# LMH6881-Breakout_Single_Layer.net
KiCad netlist of a schematic drawn in EAGLE
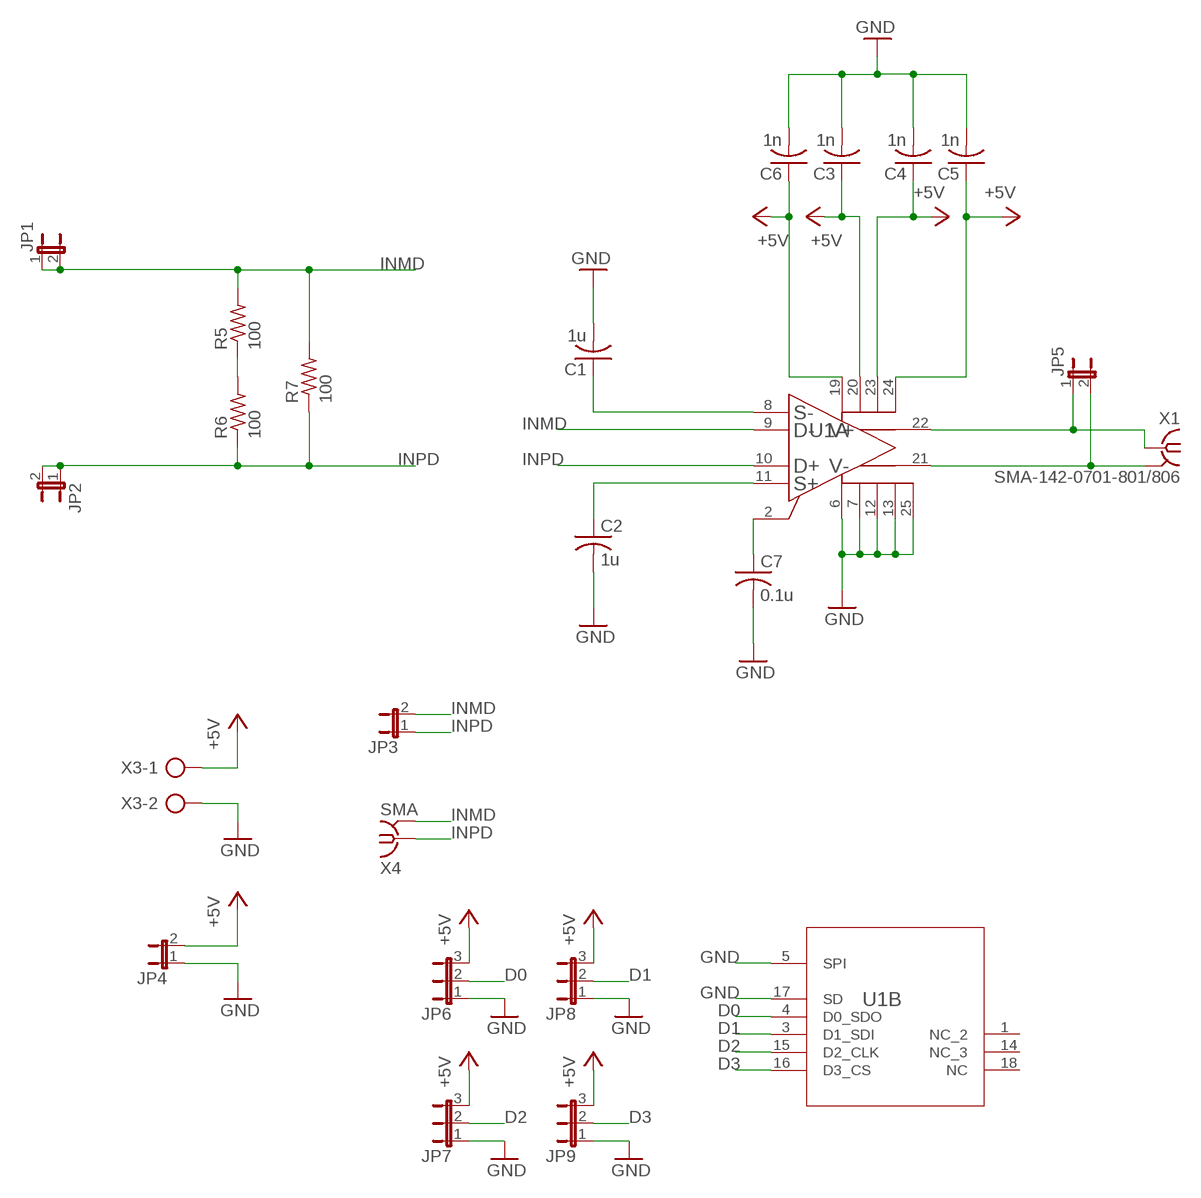
[diagram p0: schematic, sheet 1]

(export (version "E")
  (design (tool "Eeschema 10.0.6"))
  (components
    (comp (ref "C1")
      (value "1u")
      (footprint "eagle-import:C0805")
      (libsource (lib "eagle-import") (part "C-USC0805"))
    )
    (comp (ref "C2")
      (value "1u")
      (footprint "eagle-import:C0805")
      (libsource (lib "eagle-import") (part "C-USC0805"))
    )
    (comp (ref "C3")
      (value "1n")
      (footprint "eagle-import:C0805")
      (libsource (lib "eagle-import") (part "C-USC0805"))
    )
    (comp (ref "C4")
      (value "1n")
      (footprint "eagle-import:C0805")
      (libsource (lib "eagle-import") (part "C-USC0805"))
    )
    (comp (ref "C5")
      (value "1n")
      (footprint "eagle-import:C0805")
      (libsource (lib "eagle-import") (part "C-USC0805"))
    )
    (comp (ref "C6")
      (value "1n")
      (footprint "eagle-import:C0805")
      (libsource (lib "eagle-import") (part "C-USC0805"))
    )
    (comp (ref "C7")
      (value "0.1u")
      (footprint "eagle-import:C0805")
      (libsource (lib "eagle-import") (part "C-USC0805"))
    )
    (comp (ref "JP1")
      (value "JP1E")
      (footprint "eagle-import:JP1")
      (libsource (lib "eagle-import") (part "JP1E"))
    )
    (comp (ref "JP2")
      (value "JP1E")
      (footprint "eagle-import:JP1")
      (libsource (lib "eagle-import") (part "JP1E"))
    )
    (comp (ref "JP3")
      (value "JP1E")
      (footprint "eagle-import:JP1")
      (libsource (lib "eagle-import") (part "JP1E"))
    )
    (comp (ref "JP4")
      (value "JP1E")
      (footprint "eagle-import:JP1")
      (libsource (lib "eagle-import") (part "JP1E"))
    )
    (comp (ref "JP5")
      (value "JP1E")
      (footprint "eagle-import:JP1")
      (libsource (lib "eagle-import") (part "JP1E"))
    )
    (comp (ref "JP6")
      (value "JP2E")
      (footprint "eagle-import:JP2")
      (libsource (lib "eagle-import") (part "JP2E"))
    )
    (comp (ref "JP7")
      (value "JP2E")
      (footprint "eagle-import:JP2")
      (libsource (lib "eagle-import") (part "JP2E"))
    )
    (comp (ref "JP8")
      (value "JP2E")
      (footprint "eagle-import:JP2")
      (libsource (lib "eagle-import") (part "JP2E"))
    )
    (comp (ref "JP9")
      (value "JP2E")
      (footprint "eagle-import:JP2")
      (libsource (lib "eagle-import") (part "JP2E"))
    )
    (comp (ref "R5")
      (value "100")
      (footprint "eagle-import:R0805")
      (libsource (lib "eagle-import") (part "R-US_R0805"))
    )
    (comp (ref "R6")
      (value "100")
      (footprint "eagle-import:R0805")
      (libsource (lib "eagle-import") (part "R-US_R0805"))
    )
    (comp (ref "R7")
      (value "100")
      (footprint "eagle-import:R0805")
      (libsource (lib "eagle-import") (part "R-US_R0805"))
    )
    (comp (ref "U1")
      (value "LMH6881SQX/NOPB")
      (footprint "eagle-import:RTW0024A")
      (fields
        (field (name "ALTERNATEPARTNUMBER") "LMH6881SQNOPB")
        (field (name "MANUFACTURER") "Texas Instruments")
        (field (name "PARTNUMBER") "LMH6881SQXNOPB")
      )
      (libsource (lib "eagle-import") (part "LMH6881SQX/NOPB"))
    )
    (comp (ref "X1")
      (value "SMA-142-0701-801/806")
      (footprint "eagle-import:J502-ND-142-0701-801_806")
      (fields (field (name "MF") "JOHNSON COMPONENTS") (field (name "MPN") "142-0701-801"))
      (libsource (lib "eagle-import") (part "SMA-142-0701-801/806"))
    )
    (comp (ref "X3")
      (value "AK500/2")
      (footprint "eagle-import:AK500_2")
      (libsource (lib "eagle-import") (part "AK500/2"))
    )
    (comp (ref "X4")
      (value "SMA")
      (footprint "eagle-import:J502-ND-142-0701-801_806")
      (fields (field (name "MF") "JOHNSON COMPONENTS") (field (name "MPN") "142-0701-801"))
      (libsource (lib "eagle-import") (part "SMA-142-0701-801/806"))
    )
  )
  (nets
    (net (code "1") (name "+5V") (class "Default")
      (node (ref "C3") (pin "1") (pinfunction "1_1") (pintype "passive"))
      (node (ref "C4") (pin "1") (pinfunction "1_1") (pintype "passive"))
      (node (ref "C5") (pin "1") (pinfunction "1_1") (pintype "passive"))
      (node (ref "C6") (pin "1") (pinfunction "1_1") (pintype "passive"))
      (node (ref "JP4") (pin "2") (pinfunction "2_2") (pintype "passive"))
      (node (ref "JP6") (pin "3") (pinfunction "3_3") (pintype "passive"))
      (node (ref "JP7") (pin "3") (pinfunction "3_3") (pintype "passive"))
      (node (ref "JP8") (pin "3") (pinfunction "3_3") (pintype "passive"))
      (node (ref "JP9") (pin "3") (pinfunction "3_3") (pintype "passive"))
      (node (ref "U1") (pin "19") (pinfunction "VCC_2_19") (pintype "power_in"))
      (node (ref "U1") (pin "20") (pinfunction "VCC_3_20") (pintype "power_in"))
      (node (ref "U1") (pin "23") (pinfunction "VCC_4_23") (pintype "power_in"))
      (node (ref "U1") (pin "24") (pinfunction "VCC_24") (pintype "passive"))
      (node (ref "X3") (pin "1") (pinfunction "KL_1") (pintype "passive"))
    )
    (net (code "2") (name "/D0") (class "Default")
      (node (ref "JP6") (pin "2") (pinfunction "2_2") (pintype "passive"))
      (node (ref "U1") (pin "4") (pinfunction "D0_SDO_4") (pintype "bidirectional"))
    )
    (net (code "3") (name "/D1") (class "Default")
      (node (ref "JP8") (pin "2") (pinfunction "2_2") (pintype "passive"))
      (node (ref "U1") (pin "3") (pinfunction "D1_SDI_3") (pintype "input"))
    )
    (net (code "4") (name "/D2") (class "Default")
      (node (ref "JP7") (pin "2") (pinfunction "2_2") (pintype "passive"))
      (node (ref "U1") (pin "15") (pinfunction "D2_CLK_15") (pintype "input"))
    )
    (net (code "5") (name "/D3") (class "Default")
      (node (ref "JP9") (pin "2") (pinfunction "2_2") (pintype "passive"))
      (node (ref "U1") (pin "16") (pinfunction "D3_CS_16") (pintype "input"))
    )
    (net (code "6") (name "/INMD") (class "Default")
      (node (ref "JP1") (pin "1") (pinfunction "1_1") (pintype "passive"))
      (node (ref "JP1") (pin "2") (pinfunction "2_2") (pintype "passive"))
      (node (ref "JP3") (pin "2") (pinfunction "2_2") (pintype "passive"))
      (node (ref "R5") (pin "2") (pinfunction "2_2") (pintype "passive"))
      (node (ref "R7") (pin "2") (pinfunction "2_2") (pintype "passive"))
      (node (ref "U1") (pin "9") (pinfunction "INMD_9") (pintype "input"))
      (node (ref "X4") (pin "G@1") (pinfunction "2_G@1") (pintype "passive"))
      (node (ref "X4") (pin "G@2") (pinfunction "2_G@2") (pintype "passive"))
      (node (ref "X4") (pin "G@3") (pinfunction "2_G@3") (pintype "passive"))
      (node (ref "X4") (pin "G@4") (pinfunction "2_G@4") (pintype "passive"))
    )
    (net (code "7") (name "/INPD") (class "Default")
      (node (ref "JP2") (pin "1") (pinfunction "1_1") (pintype "passive"))
      (node (ref "JP2") (pin "2") (pinfunction "2_2") (pintype "passive"))
      (node (ref "JP3") (pin "1") (pinfunction "1_1") (pintype "passive"))
      (node (ref "R6") (pin "1") (pinfunction "1_1") (pintype "passive"))
      (node (ref "R7") (pin "1") (pinfunction "1_1") (pintype "passive"))
      (node (ref "U1") (pin "10") (pinfunction "INPD_10") (pintype "input"))
      (node (ref "X4") (pin "1") (pinfunction "1_1") (pintype "passive"))
    )
    (net (code "8") (name "GND") (class "Default")
      (node (ref "C1") (pin "2") (pinfunction "2_2") (pintype "passive"))
      (node (ref "C2") (pin "2") (pinfunction "2_2") (pintype "passive"))
      (node (ref "C3") (pin "2") (pinfunction "2_2") (pintype "passive"))
      (node (ref "C4") (pin "2") (pinfunction "2_2") (pintype "passive"))
      (node (ref "C5") (pin "2") (pinfunction "2_2") (pintype "passive"))
      (node (ref "C6") (pin "2") (pinfunction "2_2") (pintype "passive"))
      (node (ref "C7") (pin "2") (pinfunction "2_2") (pintype "passive"))
      (node (ref "JP4") (pin "1") (pinfunction "1_1") (pintype "passive"))
      (node (ref "JP6") (pin "1") (pinfunction "1_1") (pintype "passive"))
      (node (ref "JP7") (pin "1") (pinfunction "1_1") (pintype "passive"))
      (node (ref "JP8") (pin "1") (pinfunction "1_1") (pintype "passive"))
      (node (ref "JP9") (pin "1") (pinfunction "1_1") (pintype "passive"))
      (node (ref "U1") (pin "12") (pinfunction "GND_4_12") (pintype "power_in"))
      (node (ref "U1") (pin "13") (pinfunction "GND_13") (pintype "power_in"))
      (node (ref "U1") (pin "17") (pinfunction "SD_17") (pintype "input"))
      (node (ref "U1") (pin "25") (pinfunction "PAD_25") (pintype "passive"))
      (node (ref "U1") (pin "5") (pinfunction "SPI_5") (pintype "input"))
      (node (ref "U1") (pin "6") (pinfunction "GND_2_6") (pintype "power_in"))
      (node (ref "U1") (pin "7") (pinfunction "GND_3_7") (pintype "power_in"))
      (node (ref "X3") (pin "2") (pinfunction "KL_2") (pintype "passive"))
    )
    (net (code "9") (name "Net-(R5-Pad1)") (class "Default")
      (node (ref "R5") (pin "1") (pinfunction "1_1") (pintype "passive"))
      (node (ref "R6") (pin "2") (pinfunction "2_2") (pintype "passive"))
    )
    (net (code "10") (name "Net-(U1A-INMS)") (class "Default")
      (node (ref "C1") (pin "1") (pinfunction "1_1") (pintype "passive"))
      (node (ref "U1") (pin "8") (pinfunction "INMS_8") (pintype "input"))
    )
    (net (code "11") (name "Net-(U1A-INPS)") (class "Default")
      (node (ref "C2") (pin "1") (pinfunction "1_1") (pintype "passive"))
      (node (ref "U1") (pin "11") (pinfunction "INPS_11") (pintype "input"))
    )
    (net (code "12") (name "Net-(U1A-OCM)") (class "Default")
      (node (ref "C7") (pin "1") (pinfunction "1_1") (pintype "passive"))
      (node (ref "U1") (pin "2") (pinfunction "OCM_2") (pintype "output"))
    )
    (net (code "13") (name "Net-(U1A-OUTM)") (class "Default")
      (node (ref "JP5") (pin "2") (pinfunction "2_2") (pintype "passive"))
      (node (ref "U1") (pin "21") (pinfunction "OUTM_21") (pintype "output"))
      (node (ref "X1") (pin "G@1") (pinfunction "2_G@1") (pintype "passive"))
      (node (ref "X1") (pin "G@2") (pinfunction "2_G@2") (pintype "passive"))
      (node (ref "X1") (pin "G@3") (pinfunction "2_G@3") (pintype "passive"))
      (node (ref "X1") (pin "G@4") (pinfunction "2_G@4") (pintype "passive"))
    )
    (net (code "14") (name "Net-(U1A-OUTP)") (class "Default")
      (node (ref "JP5") (pin "1") (pinfunction "1_1") (pintype "passive"))
      (node (ref "U1") (pin "22") (pinfunction "OUTP_22") (pintype "output"))
      (node (ref "X1") (pin "1") (pinfunction "1_1") (pintype "passive"))
    )
    (net (code "15") (name "unconnected-(U1B-NC-Pad18)") (class "Default")
      (node (ref "U1") (pin "18") (pinfunction "NC_18") (pintype "passive"))
    )
    (net (code "16") (name "unconnected-(U1B-NC_2-Pad1)") (class "Default")
      (node (ref "U1") (pin "1") (pinfunction "NC_2_1") (pintype "passive"))
    )
    (net (code "17") (name "unconnected-(U1B-NC_3-Pad14)") (class "Default")
      (node (ref "U1") (pin "14") (pinfunction "NC_3_14") (pintype "passive"))
    )
  )
)
